# DSC_IO_Board.net
KiCad netlist of a schematic drawn in EAGLE
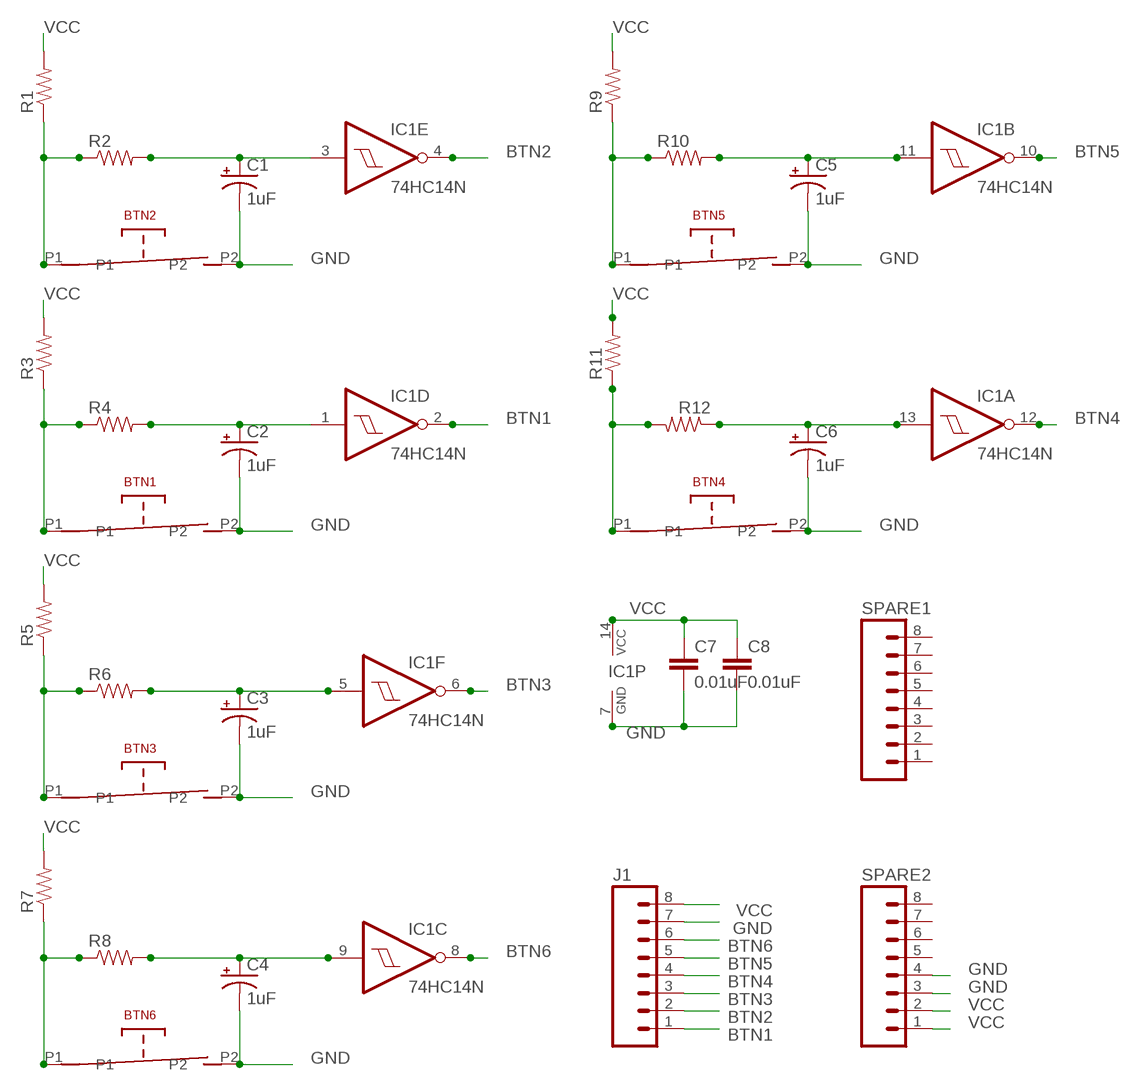
[diagram p0: schematic, sheet 1]

(export (version "E")
  (design (tool "Eeschema 10.0.6"))
  (components
    (comp (ref "BTN1")
      (value "MOMENTARY-TACTILE-SWTICH")
      (footprint "eagle-import:MOMENTARY-TACTILE-SWITCH")
      (libsource (lib "eagle-import") (part "MOMENTARY-TACTILE-SWTICH"))
    )
    (comp (ref "BTN2")
      (value "MOMENTARY-TACTILE-SWTICH")
      (footprint "eagle-import:MOMENTARY-TACTILE-SWITCH")
      (libsource (lib "eagle-import") (part "MOMENTARY-TACTILE-SWTICH"))
    )
    (comp (ref "BTN3")
      (value "MOMENTARY-TACTILE-SWTICH")
      (footprint "eagle-import:MOMENTARY-TACTILE-SWITCH")
      (libsource (lib "eagle-import") (part "MOMENTARY-TACTILE-SWTICH"))
    )
    (comp (ref "BTN4")
      (value "MOMENTARY-TACTILE-SWTICH")
      (footprint "eagle-import:MOMENTARY-TACTILE-SWITCH")
      (libsource (lib "eagle-import") (part "MOMENTARY-TACTILE-SWTICH"))
    )
    (comp (ref "BTN5")
      (value "MOMENTARY-TACTILE-SWTICH")
      (footprint "eagle-import:MOMENTARY-TACTILE-SWITCH")
      (libsource (lib "eagle-import") (part "MOMENTARY-TACTILE-SWTICH"))
    )
    (comp (ref "BTN6")
      (value "MOMENTARY-TACTILE-SWTICH")
      (footprint "eagle-import:MOMENTARY-TACTILE-SWITCH")
      (libsource (lib "eagle-import") (part "MOMENTARY-TACTILE-SWTICH"))
    )
    (comp (ref "C1")
      (value "1uF")
      (footprint "eagle-import:CPOL-RADIAL-10UF-25V-KIT")
      (libsource (lib "eagle-import") (part "10UF-25V-20%(PTH)KIT"))
    )
    (comp (ref "C2")
      (value "1uF")
      (footprint "eagle-import:CPOL-RADIAL-10UF-25V-KIT")
      (libsource (lib "eagle-import") (part "10UF-25V-20%(PTH)KIT"))
    )
    (comp (ref "C3")
      (value "1uF")
      (footprint "eagle-import:CPOL-RADIAL-10UF-25V-KIT")
      (libsource (lib "eagle-import") (part "10UF-25V-20%(PTH)KIT"))
    )
    (comp (ref "C4")
      (value "1uF")
      (footprint "eagle-import:CPOL-RADIAL-10UF-25V-KIT")
      (libsource (lib "eagle-import") (part "10UF-25V-20%(PTH)KIT"))
    )
    (comp (ref "C5")
      (value "1uF")
      (footprint "eagle-import:CPOL-RADIAL-10UF-25V-KIT")
      (libsource (lib "eagle-import") (part "10UF-25V-20%(PTH)KIT"))
    )
    (comp (ref "C6")
      (value "1uF")
      (footprint "eagle-import:CPOL-RADIAL-10UF-25V-KIT")
      (libsource (lib "eagle-import") (part "10UF-25V-20%(PTH)KIT"))
    )
    (comp (ref "C7")
      (value "0.01uF")
      (footprint "eagle-import:CAP-PTH-SMALL")
      (libsource (lib "eagle-import") (part "CAPPTH"))
    )
    (comp (ref "C8")
      (value "0.01uF")
      (footprint "eagle-import:CAP-PTH-SMALL")
      (libsource (lib "eagle-import") (part "CAPPTH"))
    )
    (comp (ref "IC1")
      (value "74HC14N")
      (footprint "eagle-import:DIL14")
      (libsource (lib "eagle-import") (part "7414NHC"))
    )
    (comp (ref "J1")
      (value "M08")
      (footprint "eagle-import:1X08_ROUND")
      (libsource (lib "eagle-import") (part "M08"))
    )
    (comp (ref "R1")
      (value "1KOHM-1/4W-1%(PTH)")
      (footprint "eagle-import:AXIAL-0.3")
      (libsource (lib "eagle-import") (part "1KOHM-1/4W-1%(PTH)"))
    )
    (comp (ref "R2")
      (value "1KOHM-1/4W-1%(PTH)")
      (footprint "eagle-import:AXIAL-0.3")
      (libsource (lib "eagle-import") (part "1KOHM-1/4W-1%(PTH)"))
    )
    (comp (ref "R3")
      (value "1KOHM-1/4W-1%(PTH)")
      (footprint "eagle-import:AXIAL-0.3")
      (libsource (lib "eagle-import") (part "1KOHM-1/4W-1%(PTH)"))
    )
    (comp (ref "R4")
      (value "1KOHM-1/4W-1%(PTH)")
      (footprint "eagle-import:AXIAL-0.3")
      (libsource (lib "eagle-import") (part "1KOHM-1/4W-1%(PTH)"))
    )
    (comp (ref "R5")
      (value "1KOHM-1/4W-1%(PTH)")
      (footprint "eagle-import:AXIAL-0.3")
      (libsource (lib "eagle-import") (part "1KOHM-1/4W-1%(PTH)"))
    )
    (comp (ref "R6")
      (value "1KOHM-1/4W-1%(PTH)")
      (footprint "eagle-import:AXIAL-0.3")
      (libsource (lib "eagle-import") (part "1KOHM-1/4W-1%(PTH)"))
    )
    (comp (ref "R7")
      (value "1KOHM-1/4W-1%(PTH)")
      (footprint "eagle-import:AXIAL-0.3")
      (libsource (lib "eagle-import") (part "1KOHM-1/4W-1%(PTH)"))
    )
    (comp (ref "R8")
      (value "1KOHM-1/4W-1%(PTH)")
      (footprint "eagle-import:AXIAL-0.3")
      (libsource (lib "eagle-import") (part "1KOHM-1/4W-1%(PTH)"))
    )
    (comp (ref "R9")
      (value "1KOHM-1/4W-1%(PTH)")
      (footprint "eagle-import:AXIAL-0.3")
      (libsource (lib "eagle-import") (part "1KOHM-1/4W-1%(PTH)"))
    )
    (comp (ref "R10")
      (value "1KOHM-1/4W-1%(PTH)")
      (footprint "eagle-import:AXIAL-0.3")
      (libsource (lib "eagle-import") (part "1KOHM-1/4W-1%(PTH)"))
    )
    (comp (ref "R11")
      (value "1KOHM-1/4W-1%(PTH)")
      (footprint "eagle-import:AXIAL-0.3")
      (libsource (lib "eagle-import") (part "1KOHM-1/4W-1%(PTH)"))
    )
    (comp (ref "R12")
      (value "1KOHM-1/4W-1%(PTH)")
      (footprint "eagle-import:AXIAL-0.3")
      (libsource (lib "eagle-import") (part "1KOHM-1/4W-1%(PTH)"))
    )
    (comp (ref "SPARE1")
      (value "M08")
      (footprint "eagle-import:1X08_ROUND")
      (libsource (lib "eagle-import") (part "M08"))
    )
    (comp (ref "SPARE2")
      (value "M08")
      (footprint "eagle-import:1X08_ROUND")
      (libsource (lib "eagle-import") (part "M08"))
    )
  )
  (nets
    (net (code "1") (name "/BTN1") (class "Default")
      (node (ref "IC1") (pin "2") (pinfunction "O_2") (pintype "output"))
      (node (ref "J1") (pin "1") (pinfunction "1_1") (pintype "passive"))
    )
    (net (code "2") (name "/BTN2") (class "Default")
      (node (ref "IC1") (pin "4") (pinfunction "O_4") (pintype "output"))
      (node (ref "J1") (pin "2") (pinfunction "2_2") (pintype "passive"))
    )
    (net (code "3") (name "/BTN3") (class "Default")
      (node (ref "IC1") (pin "6") (pinfunction "O_6") (pintype "output"))
      (node (ref "J1") (pin "3") (pinfunction "3_3") (pintype "passive"))
    )
    (net (code "4") (name "/BTN4") (class "Default")
      (node (ref "IC1") (pin "12") (pinfunction "O_12") (pintype "output"))
      (node (ref "J1") (pin "4") (pinfunction "4_4") (pintype "passive"))
    )
    (net (code "5") (name "/BTN5") (class "Default")
      (node (ref "IC1") (pin "10") (pinfunction "O_10") (pintype "output"))
      (node (ref "J1") (pin "5") (pinfunction "5_5") (pintype "passive"))
    )
    (net (code "6") (name "/BTN6") (class "Default")
      (node (ref "IC1") (pin "8") (pinfunction "O_8") (pintype "output"))
      (node (ref "J1") (pin "6") (pinfunction "6_6") (pintype "passive"))
    )
    (net (code "7") (name "/GND") (class "Default")
      (node (ref "BTN1") (pin "P2") (pinfunction "P2_P2") (pintype "bidirectional"))
      (node (ref "BTN2") (pin "P2") (pinfunction "P2_P2") (pintype "bidirectional"))
      (node (ref "BTN3") (pin "P2") (pinfunction "P2_P2") (pintype "bidirectional"))
      (node (ref "BTN4") (pin "P2") (pinfunction "P2_P2") (pintype "bidirectional"))
      (node (ref "BTN5") (pin "P2") (pinfunction "P2_P2") (pintype "bidirectional"))
      (node (ref "BTN6") (pin "P2") (pinfunction "P2_P2") (pintype "bidirectional"))
      (node (ref "C1") (pin "2") (pinfunction "-_2") (pintype "passive"))
      (node (ref "C2") (pin "2") (pinfunction "-_2") (pintype "passive"))
      (node (ref "C3") (pin "2") (pinfunction "-_2") (pintype "passive"))
      (node (ref "C4") (pin "2") (pinfunction "-_2") (pintype "passive"))
      (node (ref "C5") (pin "2") (pinfunction "-_2") (pintype "passive"))
      (node (ref "C6") (pin "2") (pinfunction "-_2") (pintype "passive"))
      (node (ref "C7") (pin "2") (pinfunction "2_2") (pintype "passive"))
      (node (ref "C8") (pin "2") (pinfunction "2_2") (pintype "passive"))
      (node (ref "IC1") (pin "7") (pinfunction "GND_7") (pintype "power_in"))
      (node (ref "J1") (pin "7") (pinfunction "7_7") (pintype "passive"))
      (node (ref "SPARE2") (pin "3") (pinfunction "3_3") (pintype "passive"))
      (node (ref "SPARE2") (pin "4") (pinfunction "4_4") (pintype "passive"))
    )
    (net (code "8") (name "/VCC") (class "Default")
      (node (ref "C7") (pin "1") (pinfunction "1_1") (pintype "passive"))
      (node (ref "C8") (pin "1") (pinfunction "1_1") (pintype "passive"))
      (node (ref "IC1") (pin "14") (pinfunction "VCC_14") (pintype "power_in"))
      (node (ref "J1") (pin "8") (pinfunction "8_8") (pintype "passive"))
      (node (ref "R1") (pin "P$2") (pinfunction "2_P$2") (pintype "passive"))
      (node (ref "R11") (pin "P$2") (pinfunction "2_P$2") (pintype "passive"))
      (node (ref "R3") (pin "P$2") (pinfunction "2_P$2") (pintype "passive"))
      (node (ref "R5") (pin "P$2") (pinfunction "2_P$2") (pintype "passive"))
      (node (ref "R7") (pin "P$2") (pinfunction "2_P$2") (pintype "passive"))
      (node (ref "R9") (pin "P$2") (pinfunction "2_P$2") (pintype "passive"))
      (node (ref "SPARE2") (pin "1") (pinfunction "1_1") (pintype "passive"))
      (node (ref "SPARE2") (pin "2") (pinfunction "2_2") (pintype "passive"))
    )
    (net (code "9") (name "Net-(C1-+)") (class "Default")
      (node (ref "C1") (pin "1") (pinfunction "+_1") (pintype "passive"))
      (node (ref "IC1") (pin "3") (pinfunction "I_3") (pintype "input"))
      (node (ref "R2") (pin "P$2") (pinfunction "2_P$2") (pintype "passive"))
    )
    (net (code "10") (name "Net-(C2-+)") (class "Default")
      (node (ref "C2") (pin "1") (pinfunction "+_1") (pintype "passive"))
      (node (ref "IC1") (pin "1") (pinfunction "I_1") (pintype "input"))
      (node (ref "R4") (pin "P$2") (pinfunction "2_P$2") (pintype "passive"))
    )
    (net (code "11") (name "Net-(C3-+)") (class "Default")
      (node (ref "C3") (pin "1") (pinfunction "+_1") (pintype "passive"))
      (node (ref "IC1") (pin "5") (pinfunction "I_5") (pintype "input"))
      (node (ref "R6") (pin "P$2") (pinfunction "2_P$2") (pintype "passive"))
    )
    (net (code "12") (name "Net-(C4-+)") (class "Default")
      (node (ref "C4") (pin "1") (pinfunction "+_1") (pintype "passive"))
      (node (ref "IC1") (pin "9") (pinfunction "I_9") (pintype "input"))
      (node (ref "R8") (pin "P$2") (pinfunction "2_P$2") (pintype "passive"))
    )
    (net (code "13") (name "Net-(C5-+)") (class "Default")
      (node (ref "C5") (pin "1") (pinfunction "+_1") (pintype "passive"))
      (node (ref "IC1") (pin "11") (pinfunction "I_11") (pintype "input"))
      (node (ref "R10") (pin "P$2") (pinfunction "2_P$2") (pintype "passive"))
    )
    (net (code "14") (name "Net-(C6-+)") (class "Default")
      (node (ref "C6") (pin "1") (pinfunction "+_1") (pintype "passive"))
      (node (ref "IC1") (pin "13") (pinfunction "I_13") (pintype "input"))
      (node (ref "R12") (pin "P$1") (pinfunction "1_P$1") (pintype "passive"))
    )
    (net (code "15") (name "Net-(R1-1)") (class "Default")
      (node (ref "BTN2") (pin "P1") (pinfunction "P1_P1") (pintype "bidirectional"))
      (node (ref "R1") (pin "P$1") (pinfunction "1_P$1") (pintype "passive"))
      (node (ref "R2") (pin "P$1") (pinfunction "1_P$1") (pintype "passive"))
    )
    (net (code "16") (name "Net-(R3-1)") (class "Default")
      (node (ref "BTN1") (pin "P1") (pinfunction "P1_P1") (pintype "bidirectional"))
      (node (ref "R3") (pin "P$1") (pinfunction "1_P$1") (pintype "passive"))
      (node (ref "R4") (pin "P$1") (pinfunction "1_P$1") (pintype "passive"))
    )
    (net (code "17") (name "Net-(R5-1)") (class "Default")
      (node (ref "BTN3") (pin "P1") (pinfunction "P1_P1") (pintype "bidirectional"))
      (node (ref "R5") (pin "P$1") (pinfunction "1_P$1") (pintype "passive"))
      (node (ref "R6") (pin "P$1") (pinfunction "1_P$1") (pintype "passive"))
    )
    (net (code "18") (name "Net-(R7-1)") (class "Default")
      (node (ref "BTN6") (pin "P1") (pinfunction "P1_P1") (pintype "bidirectional"))
      (node (ref "R7") (pin "P$1") (pinfunction "1_P$1") (pintype "passive"))
      (node (ref "R8") (pin "P$1") (pinfunction "1_P$1") (pintype "passive"))
    )
    (net (code "19") (name "Net-(R10-1)") (class "Default")
      (node (ref "BTN5") (pin "P1") (pinfunction "P1_P1") (pintype "bidirectional"))
      (node (ref "R10") (pin "P$1") (pinfunction "1_P$1") (pintype "passive"))
      (node (ref "R9") (pin "P$1") (pinfunction "1_P$1") (pintype "passive"))
    )
    (net (code "20") (name "Net-(R11-1)") (class "Default")
      (node (ref "BTN4") (pin "P1") (pinfunction "P1_P1") (pintype "bidirectional"))
      (node (ref "R11") (pin "P$1") (pinfunction "1_P$1") (pintype "passive"))
      (node (ref "R12") (pin "P$2") (pinfunction "2_P$2") (pintype "passive"))
    )
    (net (code "21") (name "unconnected-(SPARE1-Pad1)") (class "Default")
      (node (ref "SPARE1") (pin "1") (pinfunction "1_1") (pintype "passive"))
    )
    (net (code "22") (name "unconnected-(SPARE1-Pad2)") (class "Default")
      (node (ref "SPARE1") (pin "2") (pinfunction "2_2") (pintype "passive"))
    )
    (net (code "23") (name "unconnected-(SPARE1-Pad3)") (class "Default")
      (node (ref "SPARE1") (pin "3") (pinfunction "3_3") (pintype "passive"))
    )
    (net (code "24") (name "unconnected-(SPARE1-Pad4)") (class "Default")
      (node (ref "SPARE1") (pin "4") (pinfunction "4_4") (pintype "passive"))
    )
    (net (code "25") (name "unconnected-(SPARE1-Pad5)") (class "Default")
      (node (ref "SPARE1") (pin "5") (pinfunction "5_5") (pintype "passive"))
    )
    (net (code "26") (name "unconnected-(SPARE1-Pad6)") (class "Default")
      (node (ref "SPARE1") (pin "6") (pinfunction "6_6") (pintype "passive"))
    )
    (net (code "27") (name "unconnected-(SPARE1-Pad7)") (class "Default")
      (node (ref "SPARE1") (pin "7") (pinfunction "7_7") (pintype "passive"))
    )
    (net (code "28") (name "unconnected-(SPARE1-Pad8)") (class "Default")
      (node (ref "SPARE1") (pin "8") (pinfunction "8_8") (pintype "passive"))
    )
    (net (code "29") (name "unconnected-(SPARE2-Pad5)") (class "Default")
      (node (ref "SPARE2") (pin "5") (pinfunction "5_5") (pintype "passive"))
    )
    (net (code "30") (name "unconnected-(SPARE2-Pad6)") (class "Default")
      (node (ref "SPARE2") (pin "6") (pinfunction "6_6") (pintype "passive"))
    )
    (net (code "31") (name "unconnected-(SPARE2-Pad7)") (class "Default")
      (node (ref "SPARE2") (pin "7") (pinfunction "7_7") (pintype "passive"))
    )
    (net (code "32") (name "unconnected-(SPARE2-Pad8)") (class "Default")
      (node (ref "SPARE2") (pin "8") (pinfunction "8_8") (pintype "passive"))
    )
  )
)
